# TestBench_rev4.net
KiCad netlist of a schematic drawn in EAGLE
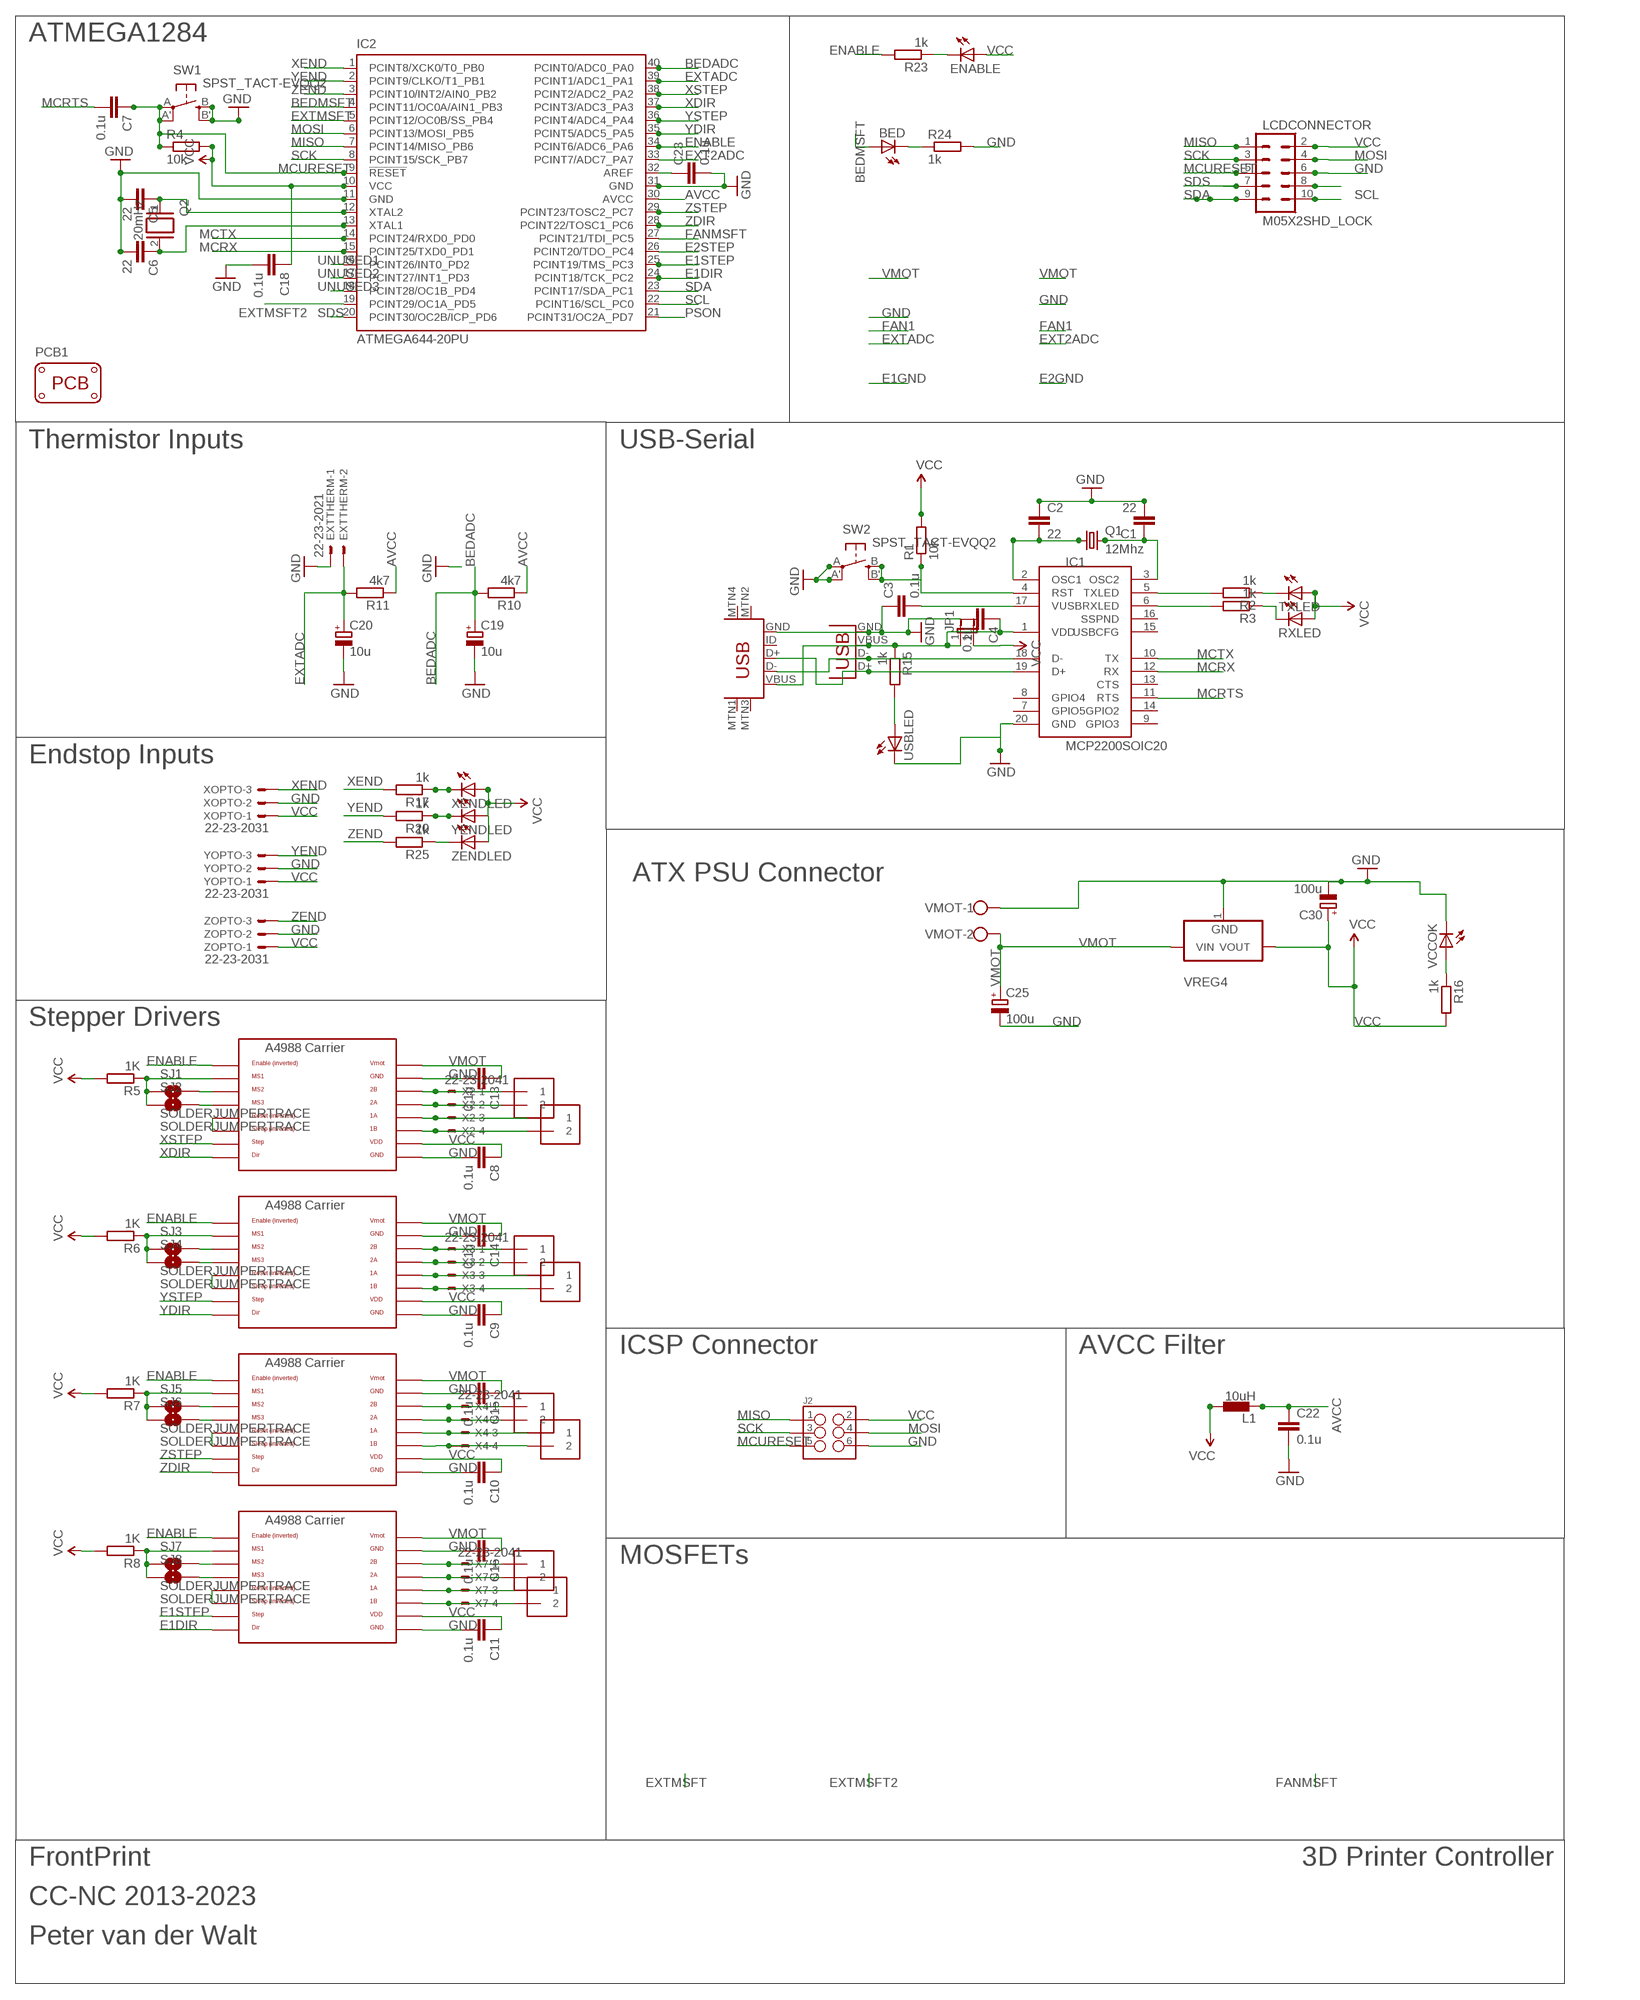
[diagram p0: schematic, sheet 1]

(export (version "E")
  (design (tool "Eeschema 10.0.6"))
  (components
    (comp (ref "BED")
      (value "LEDSMT1206")
      (footprint "eagle-import:1206")
      (libsource (lib "eagle-import") (part "LEDSMT1206"))
    )
    (comp (ref "C1")
      (value "22")
      (footprint "eagle-import:1206")
      (libsource (lib "eagle-import") (part "CAP1206"))
    )
    (comp (ref "C2")
      (value "22")
      (footprint "eagle-import:1206")
      (libsource (lib "eagle-import") (part "CAP1206"))
    )
    (comp (ref "C3")
      (value "0.1u")
      (footprint "eagle-import:1206")
      (libsource (lib "eagle-import") (part "CAP1206"))
    )
    (comp (ref "C4")
      (value "0.1u")
      (footprint "eagle-import:1206")
      (libsource (lib "eagle-import") (part "CAP1206"))
    )
    (comp (ref "C5")
      (value "22")
      (footprint "eagle-import:1206")
      (libsource (lib "eagle-import") (part "CAP1206"))
    )
    (comp (ref "C6")
      (value "22")
      (footprint "eagle-import:1206")
      (libsource (lib "eagle-import") (part "CAP1206"))
    )
    (comp (ref "C7")
      (value "0.1u")
      (footprint "eagle-import:1206")
      (libsource (lib "eagle-import") (part "CAP1206"))
    )
    (comp (ref "C8")
      (value "0.1u")
      (footprint "eagle-import:1206")
      (libsource (lib "eagle-import") (part "CAP1206"))
    )
    (comp (ref "C9")
      (value "0.1u")
      (footprint "eagle-import:1206")
      (libsource (lib "eagle-import") (part "CAP1206"))
    )
    (comp (ref "C10")
      (value "0.1u")
      (footprint "eagle-import:1206")
      (libsource (lib "eagle-import") (part "CAP1206"))
    )
    (comp (ref "C11")
      (value "0.1u")
      (footprint "eagle-import:1206")
      (libsource (lib "eagle-import") (part "CAP1206"))
    )
    (comp (ref "C13")
      (value "0.1u")
      (footprint "eagle-import:1206")
      (libsource (lib "eagle-import") (part "CAP1206"))
    )
    (comp (ref "C14")
      (value "0.1u")
      (footprint "eagle-import:1206")
      (libsource (lib "eagle-import") (part "CAP1206"))
    )
    (comp (ref "C15")
      (value "0.1u")
      (footprint "eagle-import:1206")
      (libsource (lib "eagle-import") (part "CAP1206"))
    )
    (comp (ref "C16")
      (value "0.1u")
      (footprint "eagle-import:1206")
      (libsource (lib "eagle-import") (part "CAP1206"))
    )
    (comp (ref "C18")
      (value "0.1u")
      (footprint "eagle-import:1206")
      (libsource (lib "eagle-import") (part "CAP1206"))
    )
    (comp (ref "C19")
      (value "10u")
      (footprint "eagle-import:E2,5-5")
      (libsource (lib "eagle-import") (part "CPOL-EUE2.5-5"))
    )
    (comp (ref "C20")
      (value "10u")
      (footprint "eagle-import:E2,5-5")
      (libsource (lib "eagle-import") (part "CPOL-EUE2.5-5"))
    )
    (comp (ref "C22")
      (value "0.1u")
      (footprint "eagle-import:1206")
      (libsource (lib "eagle-import") (part "CAP1206"))
    )
    (comp (ref "C23")
      (value "0.1u")
      (footprint "eagle-import:1206")
      (libsource (lib "eagle-import") (part "CAP1206"))
    )
    (comp (ref "C25")
      (value "100u")
      (footprint "eagle-import:E5-8,5")
      (libsource (lib "eagle-import") (part "CPOL-EUE5-8.5"))
    )
    (comp (ref "C30")
      (value "100u")
      (footprint "eagle-import:E5-8,5")
      (libsource (lib "eagle-import") (part "CPOL-EUE5-8.5"))
    )
    (comp (ref "E1MOT1")
      (value "1X2-3.5MM")
      (footprint "eagle-import:3.5MMTERM")
      (libsource (lib "eagle-import") (part "1X2-3.5MM"))
    )
    (comp (ref "E1MOT2")
      (value "1X2-3.5MM")
      (footprint "eagle-import:3.5MMTERM")
      (libsource (lib "eagle-import") (part "1X2-3.5MM"))
    )
    (comp (ref "ENABLE")
      (value "LEDSMT1206")
      (footprint "eagle-import:1206")
      (libsource (lib "eagle-import") (part "LEDSMT1206"))
    )
    (comp (ref "EPOLOLU")
      (value "POLOLU_A4983CARRIER")
      (footprint "eagle-import:A4988BREAKOUT")
      (libsource (lib "eagle-import") (part "POLOLU_A4983CARRIER"))
    )
    (comp (ref "EXTTHERM")
      (value "22-23-2021")
      (footprint "eagle-import:22-23-2021")
      (fields (field (name "MF") "MOLEX"))
      (libsource (lib "eagle-import") (part "22-23-2021"))
    )
    (comp (ref "IC1")
      (value "MCP2200SOIC20")
      (footprint "eagle-import:SOIC20")
      (libsource (lib "eagle-import") (part "MCP2200SOIC20"))
    )
    (comp (ref "IC2")
      (value "ATMEGA644-20PU")
      (footprint "eagle-import:DIL40")
      (libsource (lib "eagle-import") (part "ATMEGA644-PU20"))
    )
    (comp (ref "J2")
      (value "M03X2")
      (footprint "eagle-import:2X3-SHROUDED")
      (libsource (lib "eagle-import") (part "M03X2"))
    )
    (comp (ref "JP1")
      (value "JUMPER-2PTH_LOCK")
      (footprint "eagle-import:1X02_LOCK")
      (libsource (lib "eagle-import") (part "JUMPER-2PTH_LOCK"))
    )
    (comp (ref "L1")
      (value "10uH")
      (footprint "eagle-import:BL01RN1A")
      (libsource (lib "eagle-import") (part "BL01RN1A"))
    )
    (comp (ref "LCDCONNECTOR")
      (value "M05X2SHD_LOCK")
      (footprint "eagle-import:2X5-SHROUDED_LOCK")
      (libsource (lib "eagle-import") (part "M05X2SHD_LOCK"))
    )
    (comp (ref "PCB1")
      (value "PCB_DP_SQUARE-10X10")
      (footprint "eagle-import:DP100100_V1")
      (libsource (lib "eagle-import") (part "PCB_DP_SQUARE-10X10"))
    )
    (comp (ref "Q1")
      (value "12Mhz")
      (footprint "eagle-import:HC49UP")
      (libsource (lib "eagle-import") (part "CRYSTALHC49UP"))
    )
    (comp (ref "Q2")
      (value "20mHz")
      (footprint "eagle-import:QS")
      (libsource (lib "eagle-import") (part "XTAL/S"))
    )
    (comp (ref "R1")
      (value "10k")
      (footprint "eagle-import:M1206")
      (libsource (lib "eagle-import") (part "R-EU_M1206"))
    )
    (comp (ref "R2")
      (value "1k")
      (footprint "eagle-import:M1206")
      (libsource (lib "eagle-import") (part "R-EU_M1206"))
    )
    (comp (ref "R3")
      (value "1k")
      (footprint "eagle-import:M1206")
      (libsource (lib "eagle-import") (part "R-EU_M1206"))
    )
    (comp (ref "R4")
      (value "10k")
      (footprint "eagle-import:M1206")
      (libsource (lib "eagle-import") (part "R-EU_M1206"))
    )
    (comp (ref "R5")
      (value "1K")
      (footprint "eagle-import:M1206")
      (libsource (lib "eagle-import") (part "R-EU_M1206"))
    )
    (comp (ref "R6")
      (value "1K")
      (footprint "eagle-import:M1206")
      (libsource (lib "eagle-import") (part "R-EU_M1206"))
    )
    (comp (ref "R7")
      (value "1K")
      (footprint "eagle-import:M1206")
      (libsource (lib "eagle-import") (part "R-EU_M1206"))
    )
    (comp (ref "R8")
      (value "1K")
      (footprint "eagle-import:M1206")
      (libsource (lib "eagle-import") (part "R-EU_M1206"))
    )
    (comp (ref "R10")
      (value "4k7")
      (footprint "eagle-import:M1206")
      (libsource (lib "eagle-import") (part "R-EU_M1206"))
    )
    (comp (ref "R11")
      (value "4k7")
      (footprint "eagle-import:M1206")
      (libsource (lib "eagle-import") (part "R-EU_M1206"))
    )
    (comp (ref "R15")
      (value "1k")
      (footprint "eagle-import:M1206")
      (libsource (lib "eagle-import") (part "R-EU_M1206"))
    )
    (comp (ref "R16")
      (value "1k")
      (footprint "eagle-import:M1206")
      (libsource (lib "eagle-import") (part "R-EU_M1206"))
    )
    (comp (ref "R17")
      (value "1k")
      (footprint "eagle-import:M1206")
      (libsource (lib "eagle-import") (part "R-EU_M1206"))
    )
    (comp (ref "R20")
      (value "1k")
      (footprint "eagle-import:M1206")
      (libsource (lib "eagle-import") (part "R-EU_M1206"))
    )
    (comp (ref "R23")
      (value "1k")
      (footprint "eagle-import:M1206")
      (libsource (lib "eagle-import") (part "R-EU_M1206"))
    )
    (comp (ref "R24")
      (value "1k")
      (footprint "eagle-import:M1206")
      (libsource (lib "eagle-import") (part "R-EU_M1206"))
    )
    (comp (ref "R25")
      (value "1k")
      (footprint "eagle-import:M1206")
      (libsource (lib "eagle-import") (part "R-EU_M1206"))
    )
    (comp (ref "RXLED")
      (value "LEDSMT1206")
      (footprint "eagle-import:1206")
      (libsource (lib "eagle-import") (part "LEDSMT1206"))
    )
    (comp (ref "SJ1")
      (value "SOLDERJUMPERTRACE")
      (footprint "eagle-import:SJ_2S-TRACE")
      (libsource (lib "eagle-import") (part "SOLDERJUMPERTRACE"))
    )
    (comp (ref "SJ2")
      (value "SOLDERJUMPERTRACE")
      (footprint "eagle-import:SJ_2S-TRACE")
      (libsource (lib "eagle-import") (part "SOLDERJUMPERTRACE"))
    )
    (comp (ref "SJ3")
      (value "SOLDERJUMPERTRACE")
      (footprint "eagle-import:SJ_2S-TRACE")
      (libsource (lib "eagle-import") (part "SOLDERJUMPERTRACE"))
    )
    (comp (ref "SJ4")
      (value "SOLDERJUMPERTRACE")
      (footprint "eagle-import:SJ_2S-TRACE")
      (libsource (lib "eagle-import") (part "SOLDERJUMPERTRACE"))
    )
    (comp (ref "SJ5")
      (value "SOLDERJUMPERTRACE")
      (footprint "eagle-import:SJ_2S-TRACE")
      (libsource (lib "eagle-import") (part "SOLDERJUMPERTRACE"))
    )
    (comp (ref "SJ6")
      (value "SOLDERJUMPERTRACE")
      (footprint "eagle-import:SJ_2S-TRACE")
      (libsource (lib "eagle-import") (part "SOLDERJUMPERTRACE"))
    )
    (comp (ref "SJ7")
      (value "SOLDERJUMPERTRACE")
      (footprint "eagle-import:SJ_2S-TRACE")
      (libsource (lib "eagle-import") (part "SOLDERJUMPERTRACE"))
    )
    (comp (ref "SJ8")
      (value "SOLDERJUMPERTRACE")
      (footprint "eagle-import:SJ_2S-TRACE")
      (libsource (lib "eagle-import") (part "SOLDERJUMPERTRACE"))
    )
    (comp (ref "SW1")
      (value "SPST_TACT-EVQQ2")
      (footprint "eagle-import:EVQ-Q2")
      (libsource (lib "eagle-import") (part "SPST_TACT-EVQQ2"))
    )
    (comp (ref "SW2")
      (value "SPST_TACT-EVQQ2")
      (footprint "eagle-import:EVQ-Q2")
      (libsource (lib "eagle-import") (part "SPST_TACT-EVQQ2"))
    )
    (comp (ref "TXLED")
      (value "LEDSMT1206")
      (footprint "eagle-import:1206")
      (libsource (lib "eagle-import") (part "LEDSMT1206"))
    )
    (comp (ref "U$2")
      (value "USB-MINIB-5PIN")
      (footprint "eagle-import:USB-MINIB")
      (libsource (lib "eagle-import") (part "USB-MINIB-5PIN"))
    )
    (comp (ref "USBLED")
      (value "LEDSMT1206")
      (footprint "eagle-import:1206")
      (libsource (lib "eagle-import") (part "LEDSMT1206"))
    )
    (comp (ref "VCCOK")
      (value "LEDSMT1206")
      (footprint "eagle-import:1206")
      (libsource (lib "eagle-import") (part "LEDSMT1206"))
    )
    (comp (ref "VMOT")
      (value "W237-102")
      (footprint "eagle-import:W237-102")
      (fields
        (field (name "MPN") "237-102")
        (field (name "MPN_1") "237-102")
        (field (name "OC_FARNELL") "unknown")
        (field (name "OC_NEWARK") "70K9898")
      )
      (libsource (lib "eagle-import") (part "W237-102"))
    )
    (comp (ref "VREG4")
      (value "VREG_3PINS-DPAK")
      (footprint "eagle-import:DPAK")
      (libsource (lib "eagle-import") (part "VREG_3PINS-DPAK"))
    )
    (comp (ref "X1")
      (value "USBPTH")
      (footprint "eagle-import:USB-B-PTH")
      (libsource (lib "eagle-import") (part "USBPTH"))
    )
    (comp (ref "X2")
      (value "22-23-2041")
      (footprint "eagle-import:22-23-2041")
      (fields (field (name "MF") "MOLEX"))
      (libsource (lib "eagle-import") (part "22-23-2041"))
    )
    (comp (ref "X3")
      (value "22-23-2041")
      (footprint "eagle-import:22-23-2041")
      (fields (field (name "MF") "MOLEX"))
      (libsource (lib "eagle-import") (part "22-23-2041"))
    )
    (comp (ref "X4")
      (value "22-23-2041")
      (footprint "eagle-import:22-23-2041")
      (fields (field (name "MF") "MOLEX"))
      (libsource (lib "eagle-import") (part "22-23-2041"))
    )
    (comp (ref "X7")
      (value "22-23-2041")
      (footprint "eagle-import:22-23-2041")
      (fields (field (name "MF") "MOLEX"))
      (libsource (lib "eagle-import") (part "22-23-2041"))
    )
    (comp (ref "XENDLED")
      (value "LEDSMT1206")
      (footprint "eagle-import:1206")
      (libsource (lib "eagle-import") (part "LEDSMT1206"))
    )
    (comp (ref "XMOT1")
      (value "1X2-3.5MM")
      (footprint "eagle-import:3.5MMTERM")
      (libsource (lib "eagle-import") (part "1X2-3.5MM"))
    )
    (comp (ref "XMOT2")
      (value "1X2-3.5MM")
      (footprint "eagle-import:3.5MMTERM")
      (libsource (lib "eagle-import") (part "1X2-3.5MM"))
    )
    (comp (ref "XOPTO")
      (value "22-23-2031")
      (footprint "eagle-import:22-23-2031")
      (fields (field (name "MF") "MOLEX"))
      (libsource (lib "eagle-import") (part "22-23-2031"))
    )
    (comp (ref "XPOLOLU")
      (value "POLOLU_A4983CARRIER")
      (footprint "eagle-import:A4988BREAKOUT")
      (libsource (lib "eagle-import") (part "POLOLU_A4983CARRIER"))
    )
    (comp (ref "YENDLED")
      (value "LEDSMT1206")
      (footprint "eagle-import:1206")
      (libsource (lib "eagle-import") (part "LEDSMT1206"))
    )
    (comp (ref "YMOT1")
      (value "1X2-3.5MM")
      (footprint "eagle-import:3.5MMTERM")
      (libsource (lib "eagle-import") (part "1X2-3.5MM"))
    )
    (comp (ref "YMOT2")
      (value "1X2-3.5MM")
      (footprint "eagle-import:3.5MMTERM")
      (libsource (lib "eagle-import") (part "1X2-3.5MM"))
    )
    (comp (ref "YOPTO")
      (value "22-23-2031")
      (footprint "eagle-import:22-23-2031")
      (fields (field (name "MF") "MOLEX"))
      (libsource (lib "eagle-import") (part "22-23-2031"))
    )
    (comp (ref "YPOLOLU")
      (value "POLOLU_A4983CARRIER")
      (footprint "eagle-import:A4988BREAKOUT")
      (libsource (lib "eagle-import") (part "POLOLU_A4983CARRIER"))
    )
    (comp (ref "ZENDLED")
      (value "LEDSMT1206")
      (footprint "eagle-import:1206")
      (libsource (lib "eagle-import") (part "LEDSMT1206"))
    )
    (comp (ref "ZMOT1")
      (value "1X2-3.5MM")
      (footprint "eagle-import:3.5MMTERM")
      (libsource (lib "eagle-import") (part "1X2-3.5MM"))
    )
    (comp (ref "ZMOT2")
      (value "1X2-3.5MM")
      (footprint "eagle-import:3.5MMTERM")
      (libsource (lib "eagle-import") (part "1X2-3.5MM"))
    )
    (comp (ref "ZOPTO")
      (value "22-23-2031")
      (footprint "eagle-import:22-23-2031")
      (fields (field (name "MF") "MOLEX"))
      (libsource (lib "eagle-import") (part "22-23-2031"))
    )
    (comp (ref "ZPOLOLU")
      (value "POLOLU_A4983CARRIER")
      (footprint "eagle-import:A4988BREAKOUT")
      (libsource (lib "eagle-import") (part "POLOLU_A4983CARRIER"))
    )
  )
  (nets
    (net (code "1") (name "/AVCC") (class "Default")
      (node (ref "C22") (pin "1") (pinfunction "1_1") (pintype "passive"))
      (node (ref "IC2") (pin "30") (pinfunction "AVCC_30") (pintype "power_in"))
      (node (ref "L1") (pin "1") (pinfunction "1_1") (pintype "passive"))
      (node (ref "R10") (pin "1") (pinfunction "1_1") (pintype "passive"))
      (node (ref "R11") (pin "1") (pinfunction "1_1") (pintype "passive"))
    )
    (net (code "2") (name "/BEDADC") (class "Default")
      (node (ref "C19") (pin "+") (pinfunction "+_+") (pintype "passive"))
      (node (ref "IC2") (pin "40") (pinfunction "PCINT0/ADC0_PA0_40") (pintype "bidirectional"))
      (node (ref "R10") (pin "2") (pinfunction "2_2") (pintype "passive"))
    )
    (net (code "3") (name "/BEDMSFT") (class "Default")
      (node (ref "BED") (pin "A") (pinfunction "A_A") (pintype "passive"))
      (node (ref "IC2") (pin "4") (pinfunction "PCINT11/OC0A/AIN1_PB3_4") (pintype "bidirectional"))
    )
    (net (code "4") (name "/E1DIR") (class "Default")
      (node (ref "EPOLOLU") (pin "DIR") (pinfunction "DIR_DIR") (pintype "input"))
      (node (ref "IC2") (pin "24") (pinfunction "PCINT18/TCK_PC2_24") (pintype "bidirectional"))
    )
    (net (code "6") (name "/E1STEP") (class "Default")
      (node (ref "EPOLOLU") (pin "STEP") (pinfunction "STEP_STEP") (pintype "input"))
      (node (ref "IC2") (pin "25") (pinfunction "PCINT19/TMS_PC3_25") (pintype "bidirectional"))
    )
    (net (code "8") (name "/E2STEP") (class "Default")
      (node (ref "IC2") (pin "26") (pinfunction "PCINT20/TDO_PC4_26") (pintype "bidirectional"))
    )
    (net (code "9") (name "/ENABLE") (class "Default")
      (node (ref "EPOLOLU") (pin "EN") (pinfunction "EN_EN") (pintype "input"))
      (node (ref "IC2") (pin "34") (pinfunction "PCINT6/ADC6_PA6_34") (pintype "bidirectional"))
      (node (ref "R23") (pin "2") (pinfunction "2_2") (pintype "passive"))
      (node (ref "XPOLOLU") (pin "EN") (pinfunction "EN_EN") (pintype "input"))
      (node (ref "YPOLOLU") (pin "EN") (pinfunction "EN_EN") (pintype "input"))
      (node (ref "ZPOLOLU") (pin "EN") (pinfunction "EN_EN") (pintype "input"))
    )
    (net (code "10") (name "/EXT2ADC") (class "Default")
      (node (ref "IC2") (pin "33") (pinfunction "PCINT7/ADC7_PA7_33") (pintype "bidirectional"))
    )
    (net (code "11") (name "/EXTADC") (class "Default")
      (node (ref "C20") (pin "+") (pinfunction "+_+") (pintype "passive"))
      (node (ref "EXTTHERM") (pin "2") (pinfunction "S_2") (pintype "passive"))
      (node (ref "IC2") (pin "39") (pinfunction "PCINT1/ADC1_PA1_39") (pintype "bidirectional"))
      (node (ref "R11") (pin "2") (pinfunction "2_2") (pintype "passive"))
    )
    (net (code "12") (name "/EXTMSFT") (class "Default")
      (node (ref "IC2") (pin "5") (pinfunction "PCINT12/OC0B/SS_PB4_5") (pintype "bidirectional"))
    )
    (net (code "13") (name "/EXTMSFT2") (class "Default")
      (node (ref "IC2") (pin "19") (pinfunction "PCINT29/OC1A_PD5_19") (pintype "bidirectional"))
    )
    (net (code "15") (name "/FANMSFT") (class "Default")
      (node (ref "IC2") (pin "27") (pinfunction "PCINT21/TDI_PC5_27") (pintype "bidirectional"))
    )
    (net (code "16") (name "/MCRTS") (class "Default")
      (node (ref "C7") (pin "2") (pinfunction "2_2") (pintype "passive"))
      (node (ref "IC1") (pin "11") (pinfunction "RTS_11") (pintype "bidirectional"))
    )
    (net (code "17") (name "/MCRX") (class "Default")
      (node (ref "IC1") (pin "12") (pinfunction "RX_12") (pintype "bidirectional"))
      (node (ref "IC2") (pin "15") (pinfunction "PCINT25/TXD0_PD1_15") (pintype "bidirectional"))
    )
    (net (code "18") (name "/MCTX") (class "Default")
      (node (ref "IC1") (pin "10") (pinfunction "TX_10") (pintype "bidirectional"))
      (node (ref "IC2") (pin "14") (pinfunction "PCINT24/RXD0_PD0_14") (pintype "bidirectional"))
    )
    (net (code "19") (name "/MCURESET") (class "Default")
      (node (ref "C7") (pin "1") (pinfunction "1_1") (pintype "passive"))
      (node (ref "IC2") (pin "9") (pinfunction "~{RESET}_9") (pintype "input"))
      (node (ref "J2") (pin "5") (pinfunction "5_5") (pintype "bidirectional"))
      (node (ref "LCDCONNECTOR") (pin "5") (pinfunction "5_5") (pintype "passive"))
      (node (ref "R4") (pin "1") (pinfunction "1_1") (pintype "passive"))
      (node (ref "SW1") (pin "A") (pinfunction "P_A") (pintype "passive"))
      (node (ref "SW1") (pin "A'") (pinfunction "P1_A'") (pintype "passive"))
    )
    (net (code "20") (name "/MISO") (class "Default")
      (node (ref "IC2") (pin "7") (pinfunction "PCINT14/MISO_PB6_7") (pintype "bidirectional"))
      (node (ref "J2") (pin "1") (pinfunction "1_1") (pintype "bidirectional"))
      (node (ref "LCDCONNECTOR") (pin "1") (pinfunction "1_1") (pintype "passive"))
    )
    (net (code "21") (name "/MOSI") (class "Default")
      (node (ref "IC2") (pin "6") (pinfunction "PCINT13/MOSI_PB5_6") (pintype "bidirectional"))
      (node (ref "J2") (pin "4") (pinfunction "4_4") (pintype "bidirectional"))
      (node (ref "LCDCONNECTOR") (pin "4") (pinfunction "4_4") (pintype "passive"))
    )
    (net (code "22") (name "/PSON") (class "Default")
      (node (ref "IC2") (pin "21") (pinfunction "PCINT31/OC2A_PD7_21") (pintype "bidirectional"))
    )
    (net (code "23") (name "/SCK") (class "Default")
      (node (ref "IC2") (pin "8") (pinfunction "PCINT15/SCK_PB7_8") (pintype "bidirectional"))
      (node (ref "J2") (pin "3") (pinfunction "3_3") (pintype "bidirectional"))
      (node (ref "LCDCONNECTOR") (pin "3") (pinfunction "3_3") (pintype "passive"))
    )
    (net (code "24") (name "/SCL") (class "Default")
      (node (ref "IC2") (pin "22") (pinfunction "PCINT16/SCL_PC0_22") (pintype "bidirectional"))
      (node (ref "LCDCONNECTOR") (pin "10") (pinfunction "10_10") (pintype "passive"))
    )
    (net (code "25") (name "/SDA") (class "Default")
      (node (ref "IC2") (pin "23") (pinfunction "PCINT17/SDA_PC1_23") (pintype "bidirectional"))
      (node (ref "LCDCONNECTOR") (pin "9") (pinfunction "9_9") (pintype "passive"))
    )
    (net (code "26") (name "/SDS") (class "Default")
      (node (ref "IC2") (pin "20") (pinfunction "PCINT30/OC2B/ICP_PD6_20") (pintype "bidirectional"))
      (node (ref "LCDCONNECTOR") (pin "7") (pinfunction "7_7") (pintype "passive"))
    )
    (net (code "27") (name "/UNUSED1") (class "Default")
      (node (ref "IC2") (pin "16") (pinfunction "PCINT26/INT0_PD2_16") (pintype "bidirectional"))
    )
    (net (code "28") (name "/UNUSED2") (class "Default")
      (node (ref "IC2") (pin "17") (pinfunction "PCINT27/INT1_PD3_17") (pintype "bidirectional"))
    )
    (net (code "29") (name "/UNUSED3") (class "Default")
      (node (ref "IC2") (pin "18") (pinfunction "PCINT28/OC1B_PD4_18") (pintype "bidirectional"))
    )
    (net (code "30") (name "/VMOT") (class "Default")
      (node (ref "C13") (pin "1") (pinfunction "1_1") (pintype "passive"))
      (node (ref "C14") (pin "1") (pinfunction "1_1") (pintype "passive"))
      (node (ref "C15") (pin "1") (pinfunction "1_1") (pintype "passive"))
      (node (ref "C16") (pin "1") (pinfunction "1_1") (pintype "passive"))
      (node (ref "C25") (pin "+") (pinfunction "+_+") (pintype "passive"))
      (node (ref "EPOLOLU") (pin "VMOT") (pinfunction "VMOT_VMOT") (pintype "power_in"))
      (node (ref "VMOT") (pin "2") (pinfunction "KL_2") (pintype "passive"))
      (node (ref "VREG4") (pin "3") (pinfunction "VIN_3") (pintype "bidirectional"))
      (node (ref "XPOLOLU") (pin "VMOT") (pinfunction "VMOT_VMOT") (pintype "power_in"))
      (node (ref "YPOLOLU") (pin "VMOT") (pinfunction "VMOT_VMOT") (pintype "power_in"))
      (node (ref "ZPOLOLU") (pin "VMOT") (pinfunction "VMOT_VMOT") (pintype "power_in"))
    )
    (net (code "31") (name "/XDIR") (class "Default")
      (node (ref "IC2") (pin "37") (pinfunction "PCINT3/ADC3_PA3_37") (pintype "bidirectional"))
      (node (ref "XPOLOLU") (pin "DIR") (pinfunction "DIR_DIR") (pintype "input"))
    )
    (net (code "32") (name "/XEND") (class "Default")
      (node (ref "IC2") (pin "1") (pinfunction "PCINT8/XCK0/T0_PB0_1") (pintype "bidirectional"))
      (node (ref "R17") (pin "2") (pinfunction "2_2") (pintype "passive"))
      (node (ref "XOPTO") (pin "3") (pinfunction "S_3") (pintype "passive"))
    )
    (net (code "33") (name "/XSTEP") (class "Default")
      (node (ref "IC2") (pin "38") (pinfunction "PCINT2/ADC2_PA2_38") (pintype "bidirectional"))
      (node (ref "XPOLOLU") (pin "STEP") (pinfunction "STEP_STEP") (pintype "input"))
    )
    (net (code "34") (name "/YDIR") (class "Default")
      (node (ref "IC2") (pin "35") (pinfunction "PCINT5/ADC5_PA5_35") (pintype "bidirectional"))
      (node (ref "YPOLOLU") (pin "DIR") (pinfunction "DIR_DIR") (pintype "input"))
    )
    (net (code "35") (name "/YEND") (class "Default")
      (node (ref "IC2") (pin "2") (pinfunction "PCINT9/CLKO/T1_PB1_2") (pintype "bidirectional"))
      (node (ref "R20") (pin "2") (pinfunction "2_2") (pintype "passive"))
      (node (ref "YOPTO") (pin "3") (pinfunction "S_3") (pintype "passive"))
    )
    (net (code "36") (name "/YSTEP") (class "Default")
      (node (ref "IC2") (pin "36") (pinfunction "PCINT4/ADC4_PA4_36") (pintype "bidirectional"))
      (node (ref "YPOLOLU") (pin "STEP") (pinfunction "STEP_STEP") (pintype "input"))
    )
    (net (code "37") (name "/ZDIR") (class "Default")
      (node (ref "IC2") (pin "28") (pinfunction "PCINT22/TOSC1_PC6_28") (pintype "bidirectional"))
      (node (ref "ZPOLOLU") (pin "DIR") (pinfunction "DIR_DIR") (pintype "input"))
    )
    (net (code "38") (name "/ZEND") (class "Default")
      (node (ref "IC2") (pin "3") (pinfunction "PCINT10/INT2/AIN0_PB2_3") (pintype "bidirectional"))
      (node (ref "R25") (pin "2") (pinfunction "2_2") (pintype "passive"))
      (node (ref "ZOPTO") (pin "3") (pinfunction "S_3") (pintype "passive"))
    )
    (net (code "39") (name "/ZSTEP") (class "Default")
      (node (ref "IC2") (pin "29") (pinfunction "PCINT23/TOSC2_PC7_29") (pintype "bidirectional"))
      (node (ref "ZPOLOLU") (pin "STEP") (pinfunction "STEP_STEP") (pintype "input"))
    )
    (net (code "40") (name "GND") (class "Default")
      (node (ref "C1") (pin "2") (pinfunction "2_2") (pintype "passive"))
      (node (ref "C10") (pin "2") (pinfunction "2_2") (pintype "passive"))
      (node (ref "C11") (pin "2") (pinfunction "2_2") (pintype "passive"))
      (node (ref "C13") (pin "2") (pinfunction "2_2") (pintype "passive"))
      (node (ref "C14") (pin "2") (pinfunction "2_2") (pintype "passive"))
      (node (ref "C15") (pin "2") (pinfunction "2_2") (pintype "passive"))
      (node (ref "C16") (pin "2") (pinfunction "2_2") (pintype "passive"))
      (node (ref "C18") (pin "2") (pinfunction "2_2") (pintype "passive"))
      (node (ref "C19") (pin "-") (pinfunction "-_-") (pintype "passive"))
      (node (ref "C2") (pin "1") (pinfunction "1_1") (pintype "passive"))
      (node (ref "C20") (pin "-") (pinfunction "-_-") (pintype "passive"))
      (node (ref "C22") (pin "2") (pinfunction "2_2") (pintype "passive"))
      (node (ref "C23") (pin "2") (pinfunction "2_2") (pintype "passive"))
      (node (ref "C25") (pin "-") (pinfunction "-_-") (pintype "passive"))
      (node (ref "C3") (pin "1") (pinfunction "1_1") (pintype "passive"))
      (node (ref "C30") (pin "-") (pinfunction "-_-") (pintype "passive"))
      (node (ref "C4") (pin "2") (pinfunction "2_2") (pintype "passive"))
      (node (ref "C5") (pin "2") (pinfunction "2_2") (pintype "passive"))
      (node (ref "C6") (pin "2") (pinfunction "2_2") (pintype "passive"))
      (node (ref "C8") (pin "2") (pinfunction "2_2") (pintype "passive"))
      (node (ref "C9") (pin "2") (pinfunction "2_2") (pintype "passive"))
      (node (ref "EPOLOLU") (pin "GND") (pinfunction "GND_GND") (pintype "power_in"))
      (node (ref "EPOLOLU") (pin "GND@0") (pinfunction "GND_GND@0") (pintype "power_in"))
      (node (ref "EXTTHERM") (pin "1") (pinfunction "S_1") (pintype "passive"))
      (node (ref "IC1") (pin "20") (pinfunction "GND_20") (pintype "bidirectional"))
      (node (ref "IC2") (pin "11") (pinfunction "GND_11") (pintype "power_in"))
      (node (ref "IC2") (pin "31") (pinfunction "GND_31") (pintype "power_in"))
      (node (ref "J2") (pin "6") (pinfunction "6_6") (pintype "bidirectional"))
      (node (ref "LCDCONNECTOR") (pin "6") (pinfunction "6_6") (pintype "passive"))
      (node (ref "R24") (pin "2") (pinfunction "2_2") (pintype "passive"))
      (node (ref "SW1") (pin "B") (pinfunction "S_B") (pintype "passive"))
      (node (ref "SW1") (pin "B'") (pinfunction "S1_B'") (pintype "passive"))
      (node (ref "SW2") (pin "A") (pinfunction "P_A") (pintype "passive"))
      (node (ref "SW2") (pin "A'") (pinfunction "P1_A'") (pintype "passive"))
      (node (ref "U$2") (pin "GND") (pinfunction "GND_GND") (pintype "bidirectional"))
      (node (ref "USBLED") (pin "C") (pinfunction "C_C") (pintype "passive"))
      (node (ref "VCCOK") (pin "C") (pinfunction "C_C") (pintype "passive"))
      (node (ref "VMOT") (pin "1") (pinfunction "KL_1") (pintype "passive"))
      (node (ref "VREG4") (pin "1") (pinfunction "GND_1") (pintype "bidirectional"))
      (node (ref "X1") (pin "GND") (pinfunction "GND_GND") (pintype "bidirectional"))
      (node (ref "XOPTO") (pin "2") (pinfunction "S_2") (pintype "passive"))
      (node (ref "XPOLOLU") (pin "GND") (pinfunction "GND_GND") (pintype "power_in"))
      (node (ref "XPOLOLU") (pin "GND@0") (pinfunction "GND_GND@0") (pintype "power_in"))
      (node (ref "YOPTO") (pin "2") (pinfunction "S_2") (pintype "passive"))
      (node (ref "YPOLOLU") (pin "GND") (pinfunction "GND_GND") (pintype "power_in"))
      (node (ref "YPOLOLU") (pin "GND@0") (pinfunction "GND_GND@0") (pintype "power_in"))
      (node (ref "ZOPTO") (pin "2") (pinfunction "S_2") (pintype "passive"))
      (node (ref "ZPOLOLU") (pin "GND") (pinfunction "GND_GND") (pintype "power_in"))
      (node (ref "ZPOLOLU") (pin "GND@0") (pinfunction "GND_GND@0") (pintype "power_in"))
    )
    (net (code "41") (name "Net-(BED-PadC)") (class "Default")
      (node (ref "BED") (pin "C") (pinfunction "C_C") (pintype "passive"))
      (node (ref "R24") (pin "1") (pinfunction "1_1") (pintype "passive"))
    )
    (net (code "42") (name "Net-(ENABLE-PadC)") (class "Default")
      (node (ref "ENABLE") (pin "C") (pinfunction "C_C") (pintype "passive"))
      (node (ref "R23") (pin "1") (pinfunction "1_1") (pintype "passive"))
    )
    (net (code "43") (name "Net-(EPOLOLU-PadMS1)") (class "Default")
      (node (ref "EPOLOLU") (pin "MS1") (pinfunction "MS1_MS1") (pintype "input"))
      (node (ref "R8") (pin "1") (pinfunction "1_1") (pintype "passive"))
      (node (ref "SJ7") (pin "1") (pinfunction "1_1") (pintype "passive"))
      (node (ref "SJ8") (pin "1") (pinfunction "1_1") (pintype "passive"))
    )
    (net (code "44") (name "Net-(EPOLOLU-PadMS2)") (class "Default")
      (node (ref "EPOLOLU") (pin "MS2") (pinfunction "MS2_MS2") (pintype "input"))
      (node (ref "SJ7") (pin "2") (pinfunction "2_2") (pintype "passive"))
    )
    (net (code "45") (name "Net-(EPOLOLU-PadMS3)") (class "Default")
      (node (ref "EPOLOLU") (pin "MS3") (pinfunction "MS3_MS3") (pintype "input"))
      (node (ref "SJ8") (pin "2") (pinfunction "2_2") (pintype "passive"))
    )
    (net (code "46") (name "Net-(EPOLOLU-SLEEP)") (class "Default")
      (node (ref "EPOLOLU") (pin "RST") (pinfunction "RST_RST") (pintype "input"))
      (node (ref "EPOLOLU") (pin "SLP") (pinfunction "SLEEP_SLP") (pintype "input"))
    )
    (net (code "47") (name "Net-(IC1-D+)") (class "Default")
      (node (ref "IC1") (pin "19") (pinfunction "D+_19") (pintype "bidirectional"))
      (node (ref "U$2") (pin "D+") (pinfunction "D+_D+") (pintype "bidirectional"))
      (node (ref "X1") (pin "D+") (pinfunction "D+_D+") (pintype "bidirectional"))
    )
    (net (code "48") (name "Net-(IC1-D-)") (class "Default")
      (node (ref "IC1") (pin "18") (pinfunction "D-_18") (pintype "bidirectional"))
      (node (ref "U$2") (pin "D-") (pinfunction "D-_D-") (pintype "bidirectional"))
      (node (ref "X1") (pin "D-") (pinfunction "D-_D-") (pintype "bidirectional"))
    )
    (net (code "49") (name "Net-(IC1-OSC1)") (class "Default")
      (node (ref "C2") (pin "2") (pinfunction "2_2") (pintype "passive"))
      (node (ref "IC1") (pin "2") (pinfunction "OSC1_2") (pintype "bidirectional"))
      (node (ref "Q1") (pin "1") (pinfunction "1_1") (pintype "passive"))
    )
    (net (code "50") (name "Net-(IC1-OSC2)") (class "Default")
      (node (ref "C1") (pin "1") (pinfunction "1_1") (pintype "passive"))
      (node (ref "IC1") (pin "3") (pinfunction "OSC2_3") (pintype "bidirectional"))
      (node (ref "Q1") (pin "2") (pinfunction "2_2") (pintype "passive"))
    )
    (net (code "51") (name "Net-(IC1-RST)") (class "Default")
      (node (ref "IC1") (pin "4") (pinfunction "RST_4") (pintype "bidirectional"))
      (node (ref "R1") (pin "1") (pinfunction "1_1") (pintype "passive"))
      (node (ref "SW2") (pin "B") (pinfunction "S_B") (pintype "passive"))
      (node (ref "SW2") (pin "B'") (pinfunction "S1_B'") (pintype "passive"))
    )
    (net (code "52") (name "Net-(IC1-RXLED)") (class "Default")
      (node (ref "IC1") (pin "6") (pinfunction "RXLED_6") (pintype "bidirectional"))
      (node (ref "R3") (pin "2") (pinfunction "2_2") (pintype "passive"))
    )
    (net (code "53") (name "Net-(IC1-TXLED)") (class "Default")
      (node (ref "IC1") (pin "5") (pinfunction "TXLED_5") (pintype "bidirectional"))
      (node (ref "R2") (pin "2") (pinfunction "2_2") (pintype "passive"))
    )
    (net (code "54") (name "Net-(IC1-VDD)") (class "Default")
      (node (ref "C4") (pin "1") (pinfunction "1_1") (pintype "passive"))
      (node (ref "IC1") (pin "1") (pinfunction "VDD_1") (pintype "bidirectional"))
      (node (ref "JP1") (pin "1") (pinfunction "1_1") (pintype "passive"))
      (node (ref "R15") (pin "1") (pinfunction "1_1") (pintype "passive"))
      (node (ref "U$2") (pin "VBUS") (pinfunction "VBUS_VBUS") (pintype "bidirectional"))
      (node (ref "X1") (pin "VBUS") (pinfunction "VBUS_VBUS") (pintype "bidirectional"))
    )
    (net (code "55") (name "Net-(IC1-VUSB)") (class "Default")
      (node (ref "C3") (pin "2") (pinfunction "2_2") (pintype "passive"))
      (node (ref "IC1") (pin "17") (pinfunction "VUSB_17") (pintype "bidirectional"))
    )
    (net (code "56") (name "Net-(IC2-AREF)") (class "Default")
      (node (ref "C23") (pin "1") (pinfunction "1_1") (pintype "passive"))
      (node (ref "IC2") (pin "32") (pinfunction "AREF_32") (pintype "passive"))
    )
    (net (code "57") (name "Net-(IC2-XTAL1)") (class "Default")
      (node (ref "C6") (pin "1") (pinfunction "1_1") (pintype "passive"))
      (node (ref "IC2") (pin "13") (pinfunction "XTAL1_13") (pintype "input"))
      (node (ref "Q2") (pin "2") (pinfunction "2_2") (pintype "passive"))
    )
    (net (code "58") (name "Net-(IC2-XTAL2)") (class "Default")
      (node (ref "C5") (pin "1") (pinfunction "1_1") (pintype "passive"))
      (node (ref "IC2") (pin "12") (pinfunction "XTAL2_12") (pintype "output"))
      (node (ref "Q2") (pin "1") (pinfunction "1_1") (pintype "passive"))
    )
    (net (code "59") (name "Net-(R2-Pad1)") (class "Default")
      (node (ref "R2") (pin "1") (pinfunction "1_1") (pintype "passive"))
      (node (ref "TXLED") (pin "C") (pinfunction "C_C") (pintype "passive"))
    )
    (net (code "60") (name "Net-(R3-Pad1)") (class "Default")
      (node (ref "R3") (pin "1") (pinfunction "1_1") (pintype "passive"))
      (node (ref "RXLED") (pin "C") (pinfunction "C_C") (pintype "passive"))
    )
    (net (code "61") (name "Net-(R5-Pad1)") (class "Default")
      (node (ref "R5") (pin "1") (pinfunction "1_1") (pintype "passive"))
      (node (ref "SJ1") (pin "1") (pinfunction "1_1") (pintype "passive"))
      (node (ref "SJ2") (pin "1") (pinfunction "1_1") (pintype "passive"))
      (node (ref "XPOLOLU") (pin "MS1") (pinfunction "MS1_MS1") (pintype "input"))
    )
    (net (code "62") (name "Net-(R6-Pad1)") (class "Default")
      (node (ref "R6") (pin "1") (pinfunction "1_1") (pintype "passive"))
      (node (ref "SJ3") (pin "1") (pinfunction "1_1") (pintype "passive"))
      (node (ref "SJ4") (pin "1") (pinfunction "1_1") (pintype "passive"))
      (node (ref "YPOLOLU") (pin "MS1") (pinfunction "MS1_MS1") (pintype "input"))
    )
    (net (code "63") (name "Net-(R7-Pad1)") (class "Default")
      (node (ref "R7") (pin "1") (pinfunction "1_1") (pintype "passive"))
      (node (ref "SJ5") (pin "1") (pinfunction "1_1") (pintype "passive"))
      (node (ref "SJ6") (pin "1") (pinfunction "1_1") (pintype "passive"))
      (node (ref "ZPOLOLU") (pin "MS1") (pinfunction "MS1_MS1") (pintype "input"))
    )
    (net (code "64") (name "Net-(R15-Pad2)") (class "Default")
      (node (ref "R15") (pin "2") (pinfunction "2_2") (pintype "passive"))
      (node (ref "USBLED") (pin "A") (pinfunction "A_A") (pintype "passive"))
    )
    (net (code "65") (name "Net-(R16-Pad1)") (class "Default")
      (node (ref "R16") (pin "1") (pinfunction "1_1") (pintype "passive"))
      (node (ref "VCCOK") (pin "A") (pinfunction "A_A") (pintype "passive"))
    )
    (net (code "66") (name "Net-(R17-Pad1)") (class "Default")
      (node (ref "R17") (pin "1") (pinfunction "1_1") (pintype "passive"))
      (node (ref "XENDLED") (pin "C") (pinfunction "C_C") (pintype "passive"))
    )
    (net (code "67") (name "Net-(R20-Pad1)") (class "Default")
      (node (ref "R20") (pin "1") (pinfunction "1_1") (pintype "passive"))
      (node (ref "YENDLED") (pin "C") (pinfunction "C_C") (pintype "passive"))
    )
    (net (code "68") (name "Net-(R25-Pad1)") (class "Default")
      (node (ref "R25") (pin "1") (pinfunction "1_1") (pintype "passive"))
      (node (ref "ZENDLED") (pin "C") (pinfunction "C_C") (pintype "passive"))
    )
    (net (code "69") (name "Net-(SJ1-Pad2)") (class "Default")
      (node (ref "SJ1") (pin "2") (pinfunction "2_2") (pintype "passive"))
      (node (ref "XPOLOLU") (pin "MS2") (pinfunction "MS2_MS2") (pintype "input"))
    )
    (net (code "70") (name "Net-(SJ2-Pad2)") (class "Default")
      (node (ref "SJ2") (pin "2") (pinfunction "2_2") (pintype "passive"))
      (node (ref "XPOLOLU") (pin "MS3") (pinfunction "MS3_MS3") (pintype "input"))
    )
    (net (code "71") (name "Net-(SJ3-Pad2)") (class "Default")
      (node (ref "SJ3") (pin "2") (pinfunction "2_2") (pintype "passive"))
      (node (ref "YPOLOLU") (pin "MS2") (pinfunction "MS2_MS2") (pintype "input"))
    )
    (net (code "72") (name "Net-(SJ4-Pad2)") (class "Default")
      (node (ref "SJ4") (pin "2") (pinfunction "2_2") (pintype "passive"))
      (node (ref "YPOLOLU") (pin "MS3") (pinfunction "MS3_MS3") (pintype "input"))
    )
    (net (code "73") (name "Net-(SJ5-Pad2)") (class "Default")
      (node (ref "SJ5") (pin "2") (pinfunction "2_2") (pintype "passive"))
      (node (ref "ZPOLOLU") (pin "MS2") (pinfunction "MS2_MS2") (pintype "input"))
    )
    (net (code "74") (name "Net-(SJ6-Pad2)") (class "Default")
      (node (ref "SJ6") (pin "2") (pinfunction "2_2") (pintype "passive"))
      (node (ref "ZPOLOLU") (pin "MS3") (pinfunction "MS3_MS3") (pintype "input"))
    )
    (net (code "75") (name "Net-(X2A-S)") (class "Default")
      (node (ref "X2") (pin "1") (pinfunction "S_1") (pintype "passive"))
      (node (ref "XMOT1") (pin "1") (pinfunction "1_1") (pintype "passive"))
      (node (ref "XPOLOLU") (pin "2B") (pinfunction "2B_2B") (pintype "output"))
    )
    (net (code "76") (name "Net-(X2B-S)") (class "Default")
      (node (ref "X2") (pin "2") (pinfunction "S_2") (pintype "passive"))
      (node (ref "XMOT1") (pin "2") (pinfunction "2_2") (pintype "passive"))
      (node (ref "XPOLOLU") (pin "2A") (pinfunction "2A_2A") (pintype "output"))
    )
    (net (code "77") (name "Net-(X2C-S)") (class "Default")
      (node (ref "X2") (pin "3") (pinfunction "S_3") (pintype "passive"))
      (node (ref "XMOT2") (pin "1") (pinfunction "1_1") (pintype "passive"))
      (node (ref "XPOLOLU") (pin "1A") (pinfunction "1A_1A") (pintype "output"))
    )
    (net (code "78") (name "Net-(X2D-S)") (class "Default")
      (node (ref "X2") (pin "4") (pinfunction "S_4") (pintype "passive"))
      (node (ref "XMOT2") (pin "2") (pinfunction "2_2") (pintype "passive"))
      (node (ref "XPOLOLU") (pin "1B") (pinfunction "1B_1B") (pintype "output"))
    )
    (net (code "79") (name "Net-(X3A-S)") (class "Default")
      (node (ref "X3") (pin "1") (pinfunction "S_1") (pintype "passive"))
      (node (ref "YMOT1") (pin "1") (pinfunction "1_1") (pintype "passive"))
      (node (ref "YPOLOLU") (pin "2B") (pinfunction "2B_2B") (pintype "output"))
    )
    (net (code "80") (name "Net-(X3B-S)") (class "Default")
      (node (ref "X3") (pin "2") (pinfunction "S_2") (pintype "passive"))
      (node (ref "YMOT1") (pin "2") (pinfunction "2_2") (pintype "passive"))
      (node (ref "YPOLOLU") (pin "2A") (pinfunction "2A_2A") (pintype "output"))
    )
    (net (code "81") (name "Net-(X3C-S)") (class "Default")
      (node (ref "X3") (pin "3") (pinfunction "S_3") (pintype "passive"))
      (node (ref "YMOT2") (pin "1") (pinfunction "1_1") (pintype "passive"))
      (node (ref "YPOLOLU") (pin "1A") (pinfunction "1A_1A") (pintype "output"))
    )
    (net (code "82") (name "Net-(X3D-S)") (class "Default")
      (node (ref "X3") (pin "4") (pinfunction "S_4") (pintype "passive"))
      (node (ref "YMOT2") (pin "2") (pinfunction "2_2") (pintype "passive"))
      (node (ref "YPOLOLU") (pin "1B") (pinfunction "1B_1B") (pintype "output"))
    )
    (net (code "83") (name "Net-(X4A-S)") (class "Default")
      (node (ref "X4") (pin "1") (pinfunction "S_1") (pintype "passive"))
      (node (ref "ZMOT1") (pin "1") (pinfunction "1_1") (pintype "passive"))
      (node (ref "ZPOLOLU") (pin "2B") (pinfunction "2B_2B") (pintype "output"))
    )
    (net (code "84") (name "Net-(X4B-S)") (class "Default")
      (node (ref "X4") (pin "2") (pinfunction "S_2") (pintype "passive"))
      (node (ref "ZMOT1") (pin "2") (pinfunction "2_2") (pintype "passive"))
      (node (ref "ZPOLOLU") (pin "2A") (pinfunction "2A_2A") (pintype "output"))
    )
    (net (code "85") (name "Net-(X4C-S)") (class "Default")
      (node (ref "X4") (pin "3") (pinfunction "S_3") (pintype "passive"))
      (node (ref "ZMOT2") (pin "1") (pinfunction "1_1") (pintype "passive"))
      (node (ref "ZPOLOLU") (pin "1A") (pinfunction "1A_1A") (pintype "output"))
    )
    (net (code "86") (name "Net-(X4D-S)") (class "Default")
      (node (ref "X4") (pin "4") (pinfunction "S_4") (pintype "passive"))
      (node (ref "ZMOT2") (pin "2") (pinfunction "2_2") (pintype "passive"))
      (node (ref "ZPOLOLU") (pin "1B") (pinfunction "1B_1B") (pintype "output"))
    )
    (net (code "87") (name "Net-(X7A-S)") (class "Default")
      (node (ref "E1MOT1") (pin "1") (pinfunction "1_1") (pintype "passive"))
      (node (ref "EPOLOLU") (pin "2B") (pinfunction "2B_2B") (pintype "output"))
      (node (ref "X7") (pin "1") (pinfunction "S_1") (pintype "passive"))
    )
    (net (code "88") (name "Net-(X7B-S)") (class "Default")
      (node (ref "E1MOT1") (pin "2") (pinfunction "2_2") (pintype "passive"))
      (node (ref "EPOLOLU") (pin "2A") (pinfunction "2A_2A") (pintype "output"))
      (node (ref "X7") (pin "2") (pinfunction "S_2") (pintype "passive"))
    )
    (net (code "89") (name "Net-(X7C-S)") (class "Default")
      (node (ref "E1MOT2") (pin "1") (pinfunction "1_1") (pintype "passive"))
      (node (ref "EPOLOLU") (pin "1A") (pinfunction "1A_1A") (pintype "output"))
      (node (ref "X7") (pin "3") (pinfunction "S_3") (pintype "passive"))
    )
    (net (code "90") (name "Net-(X7D-S)") (class "Default")
      (node (ref "E1MOT2") (pin "2") (pinfunction "2_2") (pintype "passive"))
      (node (ref "EPOLOLU") (pin "1B") (pinfunction "1B_1B") (pintype "output"))
      (node (ref "X7") (pin "4") (pinfunction "S_4") (pintype "passive"))
    )
    (net (code "91") (name "Net-(XPOLOLU-SLEEP)") (class "Default")
      (node (ref "XPOLOLU") (pin "RST") (pinfunction "RST_RST") (pintype "input"))
      (node (ref "XPOLOLU") (pin "SLP") (pinfunction "SLEEP_SLP") (pintype "input"))
    )
    (net (code "92") (name "Net-(YPOLOLU-SLEEP)") (class "Default")
      (node (ref "YPOLOLU") (pin "RST") (pinfunction "RST_RST") (pintype "input"))
      (node (ref "YPOLOLU") (pin "SLP") (pinfunction "SLEEP_SLP") (pintype "input"))
    )
    (net (code "93") (name "Net-(ZPOLOLU-SLEEP)") (class "Default")
      (node (ref "ZPOLOLU") (pin "RST") (pinfunction "RST_RST") (pintype "input"))
      (node (ref "ZPOLOLU") (pin "SLP") (pinfunction "SLEEP_SLP") (pintype "input"))
    )
    (net (code "94") (name "VCC") (class "Default")
      (node (ref "C10") (pin "1") (pinfunction "1_1") (pintype "passive"))
      (node (ref "C11") (pin "1") (pinfunction "1_1") (pintype "passive"))
      (node (ref "C18") (pin "1") (pinfunction "1_1") (pintype "passive"))
      (node (ref "C30") (pin "+") (pinfunction "+_+") (pintype "passive"))
      (node (ref "C8") (pin "1") (pinfunction "1_1") (pintype "passive"))
      (node (ref "C9") (pin "1") (pinfunction "1_1") (pintype "passive"))
      (node (ref "ENABLE") (pin "A") (pinfunction "A_A") (pintype "passive"))
      (node (ref "EPOLOLU") (pin "VDD") (pinfunction "VDD_VDD") (pintype "power_in"))
      (node (ref "IC2") (pin "10") (pinfunction "VCC_10") (pintype "power_in"))
      (node (ref "J2") (pin "2") (pinfunction "2_2") (pintype "bidirectional"))
      (node (ref "JP1") (pin "2") (pinfunction "2_2") (pintype "passive"))
      (node (ref "L1") (pin "2") (pinfunction "2_2") (pintype "passive"))
      (node (ref "LCDCONNECTOR") (pin "2") (pinfunction "2_2") (pintype "passive"))
      (node (ref "R1") (pin "2") (pinfunction "2_2") (pintype "passive"))
      (node (ref "R16") (pin "2") (pinfunction "2_2") (pintype "passive"))
      (node (ref "R4") (pin "2") (pinfunction "2_2") (pintype "passive"))
      (node (ref "R5") (pin "2") (pinfunction "2_2") (pintype "passive"))
      (node (ref "R6") (pin "2") (pinfunction "2_2") (pintype "passive"))
      (node (ref "R7") (pin "2") (pinfunction "2_2") (pintype "passive"))
      (node (ref "R8") (pin "2") (pinfunction "2_2") (pintype "passive"))
      (node (ref "RXLED") (pin "A") (pinfunction "A_A") (pintype "passive"))
      (node (ref "TXLED") (pin "A") (pinfunction "A_A") (pintype "passive"))
      (node (ref "VREG4") (pin "2") (pinfunction "VOUT_2") (pintype "bidirectional"))
      (node (ref "XENDLED") (pin "A") (pinfunction "A_A") (pintype "passive"))
      (node (ref "XOPTO") (pin "1") (pinfunction "S_1") (pintype "passive"))
      (node (ref "XPOLOLU") (pin "VDD") (pinfunction "VDD_VDD") (pintype "power_in"))
      (node (ref "YENDLED") (pin "A") (pinfunction "A_A") (pintype "passive"))
      (node (ref "YOPTO") (pin "1") (pinfunction "S_1") (pintype "passive"))
      (node (ref "YPOLOLU") (pin "VDD") (pinfunction "VDD_VDD") (pintype "power_in"))
      (node (ref "ZENDLED") (pin "A") (pinfunction "A_A") (pintype "passive"))
      (node (ref "ZOPTO") (pin "1") (pinfunction "S_1") (pintype "passive"))
      (node (ref "ZPOLOLU") (pin "VDD") (pinfunction "VDD_VDD") (pintype "power_in"))
    )
    (net (code "95") (name "unconnected-(IC1-CTS-Pad13)") (class "Default")
      (node (ref "IC1") (pin "13") (pinfunction "CTS_13") (pintype "bidirectional"))
    )
    (net (code "96") (name "unconnected-(IC1-GPIO2-Pad14)") (class "Default")
      (node (ref "IC1") (pin "14") (pinfunction "GPIO2_14") (pintype "bidirectional"))
    )
    (net (code "97") (name "unconnected-(IC1-GPIO3-Pad9)") (class "Default")
      (node (ref "IC1") (pin "9") (pinfunction "GPIO3_9") (pintype "bidirectional"))
    )
    (net (code "98") (name "unconnected-(IC1-GPIO4-Pad8)") (class "Default")
      (node (ref "IC1") (pin "8") (pinfunction "GPIO4_8") (pintype "bidirectional"))
    )
    (net (code "99") (name "unconnected-(IC1-GPIO5-Pad7)") (class "Default")
      (node (ref "IC1") (pin "7") (pinfunction "GPIO5_7") (pintype "bidirectional"))
    )
    (net (code "100") (name "unconnected-(IC1-SSPND-Pad16)") (class "Default")
      (node (ref "IC1") (pin "16") (pinfunction "SSPND_16") (pintype "bidirectional"))
    )
    (net (code "101") (name "unconnected-(IC1-USBCFG-Pad15)") (class "Default")
      (node (ref "IC1") (pin "15") (pinfunction "USBCFG_15") (pintype "bidirectional"))
    )
    (net (code "102") (name "unconnected-(LCDCONNECTOR-Pad8)") (class "Default")
      (node (ref "LCDCONNECTOR") (pin "8") (pinfunction "8_8") (pintype "passive"))
    )
    (net (code "103") (name "unconnected-(U$2-MTN1-PadMTN3)") (class "Default")
      (node (ref "U$2") (pin "MTN3") (pinfunction "MTN1_MTN3") (pintype "bidirectional"))
    )
    (net (code "104") (name "unconnected-(U$2-MTN2-PadMTN1)") (class "Default")
      (node (ref "U$2") (pin "MTN1") (pinfunction "MTN2_MTN1") (pintype "bidirectional"))
    )
    (net (code "105") (name "unconnected-(U$2-MTN3-PadMTN2)") (class "Default")
      (node (ref "U$2") (pin "MTN2") (pinfunction "MTN3_MTN2") (pintype "bidirectional"))
    )
    (net (code "106") (name "unconnected-(U$2-PadID)") (class "Default")
      (node (ref "U$2") (pin "ID") (pinfunction "ID_ID") (pintype "bidirectional"))
    )
    (net (code "107") (name "unconnected-(U$2-PadMTN4)") (class "Default")
      (node (ref "U$2") (pin "MTN4") (pinfunction "MTN4_MTN4") (pintype "bidirectional"))
    )
  )
)
